# board.net
KiCad netlist of a schematic drawn in EAGLE
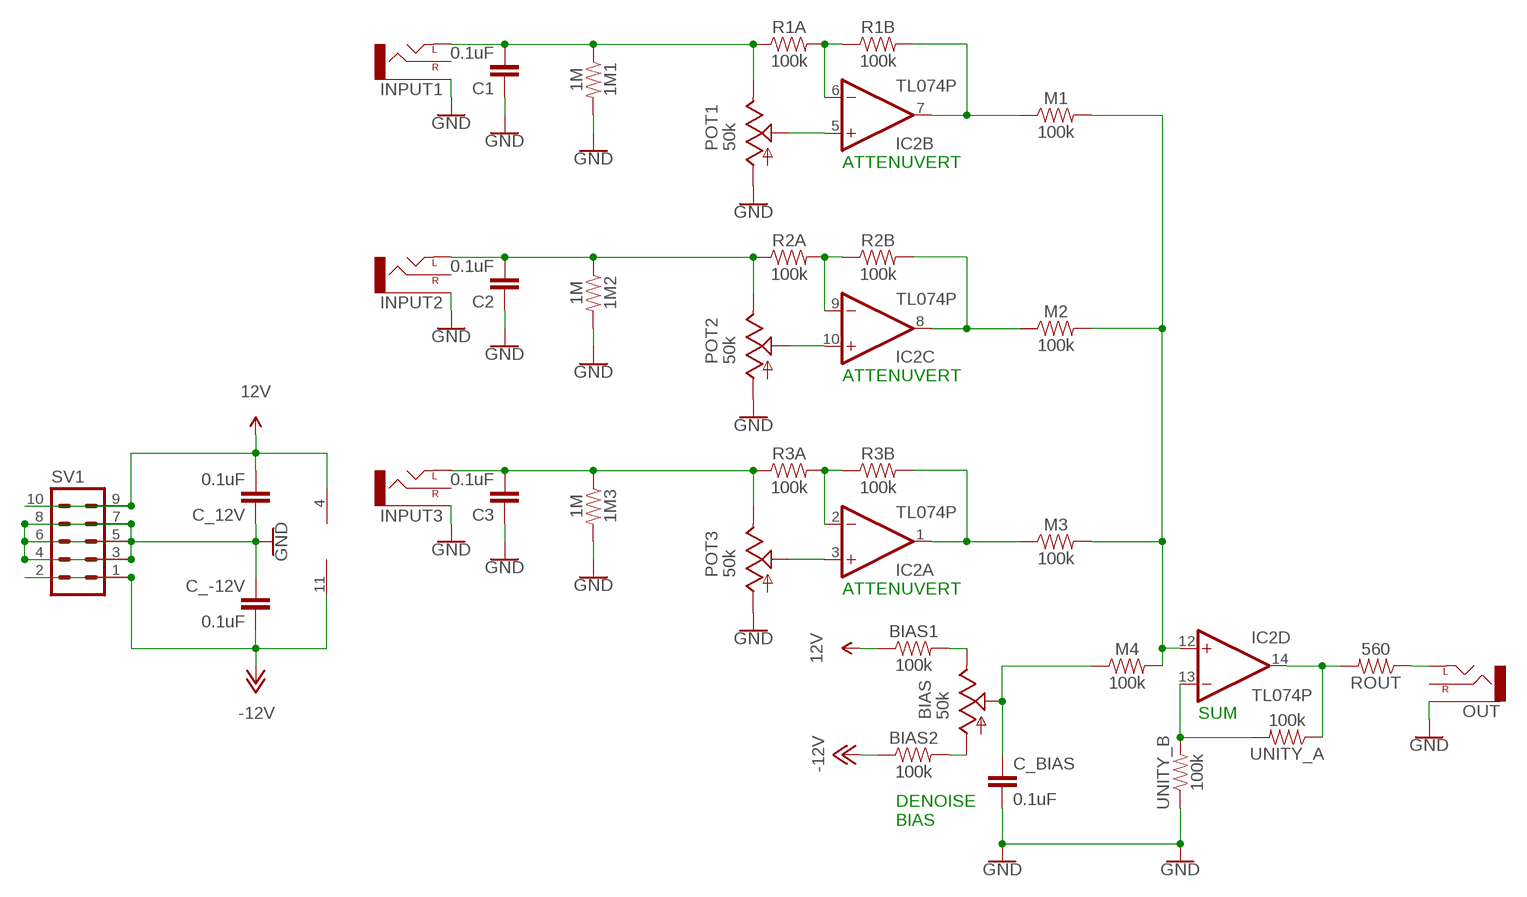
[diagram p0: schematic, sheet 1]

(export (version "E")
  (design (tool "Eeschema 10.0.6"))
  (components
    (comp (ref "1M1")
      (value "1M")
      (footprint "eagle-import:AXIAL-0.3")
      (libsource (lib "eagle-import") (part "1MOHM-HORIZ-1/4W-5%"))
    )
    (comp (ref "1M2")
      (value "1M")
      (footprint "eagle-import:AXIAL-0.3")
      (libsource (lib "eagle-import") (part "1MOHM-HORIZ-1/4W-5%"))
    )
    (comp (ref "1M3")
      (value "1M")
      (footprint "eagle-import:AXIAL-0.3")
      (libsource (lib "eagle-import") (part "1MOHM-HORIZ-1/4W-5%"))
    )
    (comp (ref "BIAS")
      (value "50k")
      (footprint "eagle-import:9MM_SNAP-IN_POT")
      (libsource (lib "eagle-import") (part "9MM_SNAP-IN_POT_"))
    )
    (comp (ref "BIAS1")
      (value "100k")
      (footprint "eagle-import:AXIAL-0.3")
      (libsource (lib "eagle-import") (part "100KOHM-HORIZ-1/4W-1%"))
    )
    (comp (ref "BIAS2")
      (value "100k")
      (footprint "eagle-import:AXIAL-0.3")
      (libsource (lib "eagle-import") (part "100KOHM-HORIZ-1/4W-1%"))
    )
    (comp (ref "C1")
      (value "0.1uF")
      (footprint "eagle-import:CAP-PTH-SMALL-KIT")
      (libsource (lib "eagle-import") (part "0.1UF-KIT-EZ-50V-20%"))
    )
    (comp (ref "C2")
      (value "0.1uF")
      (footprint "eagle-import:CAP-PTH-SMALL-KIT")
      (libsource (lib "eagle-import") (part "0.1UF-KIT-EZ-50V-20%"))
    )
    (comp (ref "C3")
      (value "0.1uF")
      (footprint "eagle-import:CAP-PTH-SMALL-KIT")
      (libsource (lib "eagle-import") (part "0.1UF-KIT-EZ-50V-20%"))
    )
    (comp (ref "C_-12V")
      (value "0.1uF")
      (footprint "eagle-import:CAP-PTH-SMALL-KIT")
      (libsource (lib "eagle-import") (part "0.1UF-KIT-EZ-50V-20%"))
    )
    (comp (ref "C_12V")
      (value "0.1uF")
      (footprint "eagle-import:CAP-PTH-SMALL-KIT")
      (libsource (lib "eagle-import") (part "0.1UF-KIT-EZ-50V-20%"))
    )
    (comp (ref "C_BIAS")
      (value "0.1uF")
      (footprint "eagle-import:CAP-PTH-SMALL-KIT")
      (libsource (lib "eagle-import") (part "0.1UF-KIT-EZ-50V-20%"))
    )
    (comp (ref "IC2")
      (value "TL074P")
      (footprint "eagle-import:DIL14")
      (libsource (lib "eagle-import") (part "TL074P"))
    )
    (comp (ref "INPUT1")
      (value "THONKI-STEREO")
      (footprint "eagle-import:WQP-PJ366ST_JACK")
      (libsource (lib "eagle-import") (part "THONKI-STEREO"))
    )
    (comp (ref "INPUT2")
      (value "THONKI-STEREO")
      (footprint "eagle-import:WQP-PJ366ST_JACK")
      (libsource (lib "eagle-import") (part "THONKI-STEREO"))
    )
    (comp (ref "INPUT3")
      (value "THONKI-STEREO")
      (footprint "eagle-import:WQP-PJ366ST_JACK")
      (libsource (lib "eagle-import") (part "THONKI-STEREO"))
    )
    (comp (ref "M1")
      (value "100k")
      (footprint "eagle-import:AXIAL-0.3")
      (libsource (lib "eagle-import") (part "100KOHM-HORIZ-1/4W-1%"))
    )
    (comp (ref "M2")
      (value "100k")
      (footprint "eagle-import:AXIAL-0.3")
      (libsource (lib "eagle-import") (part "100KOHM-HORIZ-1/4W-1%"))
    )
    (comp (ref "M3")
      (value "100k")
      (footprint "eagle-import:AXIAL-0.3")
      (libsource (lib "eagle-import") (part "100KOHM-HORIZ-1/4W-1%"))
    )
    (comp (ref "M4")
      (value "100k")
      (footprint "eagle-import:AXIAL-0.3")
      (libsource (lib "eagle-import") (part "100KOHM-HORIZ-1/4W-1%"))
    )
    (comp (ref "OUT")
      (value "THONKI-STEREO")
      (footprint "eagle-import:WQP-PJ366ST_JACK")
      (libsource (lib "eagle-import") (part "THONKI-STEREO"))
    )
    (comp (ref "POT1")
      (value "50k")
      (footprint "eagle-import:9MM_SNAP-IN_POT")
      (libsource (lib "eagle-import") (part "9MM_SNAP-IN_POT_"))
    )
    (comp (ref "POT2")
      (value "50k")
      (footprint "eagle-import:9MM_SNAP-IN_POT")
      (libsource (lib "eagle-import") (part "9MM_SNAP-IN_POT_"))
    )
    (comp (ref "POT3")
      (value "50k")
      (footprint "eagle-import:9MM_SNAP-IN_POT")
      (libsource (lib "eagle-import") (part "9MM_SNAP-IN_POT_"))
    )
    (comp (ref "R1A")
      (value "100k")
      (footprint "eagle-import:AXIAL-0.3")
      (libsource (lib "eagle-import") (part "100KOHM-HORIZ-1/4W-1%"))
    )
    (comp (ref "R1B")
      (value "100k")
      (footprint "eagle-import:AXIAL-0.3")
      (libsource (lib "eagle-import") (part "100KOHM-HORIZ-1/4W-1%"))
    )
    (comp (ref "R2A")
      (value "100k")
      (footprint "eagle-import:AXIAL-0.3")
      (libsource (lib "eagle-import") (part "100KOHM-HORIZ-1/4W-1%"))
    )
    (comp (ref "R2B")
      (value "100k")
      (footprint "eagle-import:AXIAL-0.3")
      (libsource (lib "eagle-import") (part "100KOHM-HORIZ-1/4W-1%"))
    )
    (comp (ref "R3A")
      (value "100k")
      (footprint "eagle-import:AXIAL-0.3")
      (libsource (lib "eagle-import") (part "100KOHM-HORIZ-1/4W-1%"))
    )
    (comp (ref "R3B")
      (value "100k")
      (footprint "eagle-import:AXIAL-0.3")
      (libsource (lib "eagle-import") (part "100KOHM-HORIZ-1/4W-1%"))
    )
    (comp (ref "ROUT")
      (value "560")
      (footprint "eagle-import:AXIAL-0.3")
      (libsource (lib "eagle-import") (part "100KOHM-HORIZ-1/4W-1%"))
    )
    (comp (ref "SV1")
      (value "EURO_POWER_HEADERFAT_PADS")
      (footprint "eagle-import:EURO_PWR_HEADER_FAT")
      (libsource (lib "eagle-import") (part "EURO_POWER_HEADERFAT_PADS"))
    )
    (comp (ref "UNITY_A")
      (value "100k")
      (footprint "eagle-import:AXIAL-0.3")
      (libsource (lib "eagle-import") (part "100KOHM-HORIZ-1/4W-1%"))
    )
    (comp (ref "UNITY_B")
      (value "100k")
      (footprint "eagle-import:AXIAL-0.3")
      (libsource (lib "eagle-import") (part "100KOHM-HORIZ-1/4W-1%"))
    )
  )
  (nets
    (net (code "1") (name "-12V") (class "Default")
      (node (ref "BIAS2") (pin "P$1") (pinfunction "1_P$1") (pintype "passive"))
      (node (ref "C_-12V") (pin "2") (pinfunction "2_2") (pintype "passive"))
      (node (ref "IC2") (pin "11") (pinfunction "V-_11") (pintype "power_in"))
      (node (ref "SV1") (pin "1") (pinfunction "1_1") (pintype "passive"))
      (node (ref "SV1") (pin "2") (pinfunction "2_2") (pintype "passive"))
    )
    (net (code "2") (name "12V") (class "Default")
      (node (ref "BIAS1") (pin "P$1") (pinfunction "1_P$1") (pintype "passive"))
      (node (ref "C_12V") (pin "2") (pinfunction "2_2") (pintype "passive"))
      (node (ref "IC2") (pin "4") (pinfunction "V+_4") (pintype "power_in"))
      (node (ref "SV1") (pin "10") (pinfunction "10_10") (pintype "passive"))
      (node (ref "SV1") (pin "9") (pinfunction "9_9") (pintype "passive"))
    )
    (net (code "3") (name "GND") (class "Default")
      (node (ref "1M1") (pin "P$2") (pinfunction "2_P$2") (pintype "passive"))
      (node (ref "1M2") (pin "P$2") (pinfunction "2_P$2") (pintype "passive"))
      (node (ref "1M3") (pin "P$2") (pinfunction "2_P$2") (pintype "passive"))
      (node (ref "C1") (pin "1") (pinfunction "1_1") (pintype "passive"))
      (node (ref "C2") (pin "1") (pinfunction "1_1") (pintype "passive"))
      (node (ref "C3") (pin "1") (pinfunction "1_1") (pintype "passive"))
      (node (ref "C_-12V") (pin "1") (pinfunction "1_1") (pintype "passive"))
      (node (ref "C_12V") (pin "1") (pinfunction "1_1") (pintype "passive"))
      (node (ref "C_BIAS") (pin "2") (pinfunction "2_2") (pintype "passive"))
      (node (ref "INPUT1") (pin "P$3_SLEEVE") (pinfunction "SLEEVE_P$3_SLEEVE") (pintype "bidirectional"))
      (node (ref "INPUT2") (pin "P$3_SLEEVE") (pinfunction "SLEEVE_P$3_SLEEVE") (pintype "bidirectional"))
      (node (ref "INPUT3") (pin "P$3_SLEEVE") (pinfunction "SLEEVE_P$3_SLEEVE") (pintype "bidirectional"))
      (node (ref "OUT") (pin "P$3_SLEEVE") (pinfunction "SLEEVE_P$3_SLEEVE") (pintype "bidirectional"))
      (node (ref "POT1") (pin "1") (pinfunction "A_1") (pintype "passive"))
      (node (ref "POT2") (pin "1") (pinfunction "A_1") (pintype "passive"))
      (node (ref "POT3") (pin "1") (pinfunction "A_1") (pintype "passive"))
      (node (ref "SV1") (pin "3") (pinfunction "3_3") (pintype "passive"))
      (node (ref "SV1") (pin "4") (pinfunction "4_4") (pintype "passive"))
      (node (ref "SV1") (pin "5") (pinfunction "5_5") (pintype "passive"))
      (node (ref "SV1") (pin "6") (pinfunction "6_6") (pintype "passive"))
      (node (ref "SV1") (pin "7") (pinfunction "7_7") (pintype "passive"))
      (node (ref "SV1") (pin "8") (pinfunction "8_8") (pintype "passive"))
      (node (ref "UNITY_B") (pin "P$1") (pinfunction "1_P$1") (pintype "passive"))
    )
    (net (code "4") (name "Net-(1M1-1)") (class "Default")
      (node (ref "1M1") (pin "P$1") (pinfunction "1_P$1") (pintype "passive"))
      (node (ref "C1") (pin "2") (pinfunction "2_2") (pintype "passive"))
      (node (ref "INPUT1") (pin "P$1_TIP") (pinfunction "LEFT_P$1_TIP") (pintype "bidirectional"))
      (node (ref "POT1") (pin "3") (pinfunction "E_3") (pintype "passive"))
      (node (ref "R1A") (pin "P$1") (pinfunction "1_P$1") (pintype "passive"))
    )
    (net (code "5") (name "Net-(1M2-1)") (class "Default")
      (node (ref "1M2") (pin "P$1") (pinfunction "1_P$1") (pintype "passive"))
      (node (ref "C2") (pin "2") (pinfunction "2_2") (pintype "passive"))
      (node (ref "INPUT2") (pin "P$1_TIP") (pinfunction "LEFT_P$1_TIP") (pintype "bidirectional"))
      (node (ref "POT2") (pin "3") (pinfunction "E_3") (pintype "passive"))
      (node (ref "R2A") (pin "P$1") (pinfunction "1_P$1") (pintype "passive"))
    )
    (net (code "6") (name "Net-(1M3-1)") (class "Default")
      (node (ref "1M3") (pin "P$1") (pinfunction "1_P$1") (pintype "passive"))
      (node (ref "C3") (pin "2") (pinfunction "2_2") (pintype "passive"))
      (node (ref "INPUT3") (pin "P$1_TIP") (pinfunction "LEFT_P$1_TIP") (pintype "bidirectional"))
      (node (ref "POT3") (pin "3") (pinfunction "E_3") (pintype "passive"))
      (node (ref "R3A") (pin "P$1") (pinfunction "1_P$1") (pintype "passive"))
    )
    (net (code "7") (name "Net-(BIAS-A)") (class "Default")
      (node (ref "BIAS") (pin "1") (pinfunction "A_1") (pintype "passive"))
      (node (ref "BIAS2") (pin "P$2") (pinfunction "2_P$2") (pintype "passive"))
    )
    (net (code "8") (name "Net-(BIAS-E)") (class "Default")
      (node (ref "BIAS") (pin "3") (pinfunction "E_3") (pintype "passive"))
      (node (ref "BIAS1") (pin "P$2") (pinfunction "2_P$2") (pintype "passive"))
    )
    (net (code "9") (name "Net-(BIAS-S)") (class "Default")
      (node (ref "BIAS") (pin "2") (pinfunction "S_2") (pintype "passive"))
      (node (ref "C_BIAS") (pin "1") (pinfunction "1_1") (pintype "passive"))
      (node (ref "M4") (pin "P$1") (pinfunction "1_P$1") (pintype "passive"))
    )
    (net (code "10") (name "Net-(IC2A-+IN)") (class "Default")
      (node (ref "IC2") (pin "3") (pinfunction "+IN_3") (pintype "input"))
      (node (ref "POT3") (pin "2") (pinfunction "S_2") (pintype "passive"))
    )
    (net (code "11") (name "Net-(IC2A--IN)") (class "Default")
      (node (ref "IC2") (pin "2") (pinfunction "-IN_2") (pintype "input"))
      (node (ref "R3A") (pin "P$2") (pinfunction "2_P$2") (pintype "passive"))
      (node (ref "R3B") (pin "P$1") (pinfunction "1_P$1") (pintype "passive"))
    )
    (net (code "12") (name "Net-(IC2A-OUT)") (class "Default")
      (node (ref "IC2") (pin "1") (pinfunction "OUT_1") (pintype "output"))
      (node (ref "M3") (pin "P$1") (pinfunction "1_P$1") (pintype "passive"))
      (node (ref "R3B") (pin "P$2") (pinfunction "2_P$2") (pintype "passive"))
    )
    (net (code "13") (name "Net-(IC2B-+IN)") (class "Default")
      (node (ref "IC2") (pin "5") (pinfunction "+IN_5") (pintype "input"))
      (node (ref "POT1") (pin "2") (pinfunction "S_2") (pintype "passive"))
    )
    (net (code "14") (name "Net-(IC2B--IN)") (class "Default")
      (node (ref "IC2") (pin "6") (pinfunction "-IN_6") (pintype "input"))
      (node (ref "R1A") (pin "P$2") (pinfunction "2_P$2") (pintype "passive"))
      (node (ref "R1B") (pin "P$1") (pinfunction "1_P$1") (pintype "passive"))
    )
    (net (code "15") (name "Net-(IC2B-OUT)") (class "Default")
      (node (ref "IC2") (pin "7") (pinfunction "OUT_7") (pintype "output"))
      (node (ref "M1") (pin "P$1") (pinfunction "1_P$1") (pintype "passive"))
      (node (ref "R1B") (pin "P$2") (pinfunction "2_P$2") (pintype "passive"))
    )
    (net (code "16") (name "Net-(IC2C-+IN)") (class "Default")
      (node (ref "IC2") (pin "10") (pinfunction "+IN_10") (pintype "input"))
      (node (ref "POT2") (pin "2") (pinfunction "S_2") (pintype "passive"))
    )
    (net (code "17") (name "Net-(IC2C--IN)") (class "Default")
      (node (ref "IC2") (pin "9") (pinfunction "-IN_9") (pintype "input"))
      (node (ref "R2A") (pin "P$2") (pinfunction "2_P$2") (pintype "passive"))
      (node (ref "R2B") (pin "P$1") (pinfunction "1_P$1") (pintype "passive"))
    )
    (net (code "18") (name "Net-(IC2C-OUT)") (class "Default")
      (node (ref "IC2") (pin "8") (pinfunction "OUT_8") (pintype "output"))
      (node (ref "M2") (pin "P$1") (pinfunction "1_P$1") (pintype "passive"))
      (node (ref "R2B") (pin "P$2") (pinfunction "2_P$2") (pintype "passive"))
    )
    (net (code "19") (name "Net-(IC2D-+IN)") (class "Default")
      (node (ref "IC2") (pin "12") (pinfunction "+IN_12") (pintype "input"))
      (node (ref "M1") (pin "P$2") (pinfunction "2_P$2") (pintype "passive"))
      (node (ref "M2") (pin "P$2") (pinfunction "2_P$2") (pintype "passive"))
      (node (ref "M3") (pin "P$2") (pinfunction "2_P$2") (pintype "passive"))
      (node (ref "M4") (pin "P$2") (pinfunction "2_P$2") (pintype "passive"))
    )
    (net (code "20") (name "Net-(IC2D--IN)") (class "Default")
      (node (ref "IC2") (pin "13") (pinfunction "-IN_13") (pintype "input"))
      (node (ref "UNITY_A") (pin "P$2") (pinfunction "2_P$2") (pintype "passive"))
      (node (ref "UNITY_B") (pin "P$2") (pinfunction "2_P$2") (pintype "passive"))
    )
    (net (code "21") (name "Net-(IC2D-OUT)") (class "Default")
      (node (ref "IC2") (pin "14") (pinfunction "OUT_14") (pintype "output"))
      (node (ref "ROUT") (pin "P$2") (pinfunction "2_P$2") (pintype "passive"))
      (node (ref "UNITY_A") (pin "P$1") (pinfunction "1_P$1") (pintype "passive"))
    )
    (net (code "22") (name "Net-(OUT-LEFT)") (class "Default")
      (node (ref "OUT") (pin "P$1_TIP") (pinfunction "LEFT_P$1_TIP") (pintype "bidirectional"))
      (node (ref "ROUT") (pin "P$1") (pinfunction "1_P$1") (pintype "passive"))
    )
    (net (code "23") (name "unconnected-(INPUT1-RIGHT-PadP$2_SWITCH)") (class "Default")
      (node (ref "INPUT1") (pin "P$2_SWITCH") (pinfunction "RIGHT_P$2_SWITCH") (pintype "bidirectional"))
    )
    (net (code "24") (name "unconnected-(INPUT2-RIGHT-PadP$2_SWITCH)") (class "Default")
      (node (ref "INPUT2") (pin "P$2_SWITCH") (pinfunction "RIGHT_P$2_SWITCH") (pintype "bidirectional"))
    )
    (net (code "25") (name "unconnected-(INPUT3-RIGHT-PadP$2_SWITCH)") (class "Default")
      (node (ref "INPUT3") (pin "P$2_SWITCH") (pinfunction "RIGHT_P$2_SWITCH") (pintype "bidirectional"))
    )
    (net (code "26") (name "unconnected-(OUT-RIGHT-PadP$2_SWITCH)") (class "Default")
      (node (ref "OUT") (pin "P$2_SWITCH") (pinfunction "RIGHT_P$2_SWITCH") (pintype "bidirectional"))
    )
  )
)
